# switch.net
KiCad netlist of a schematic drawn in Altium Designer
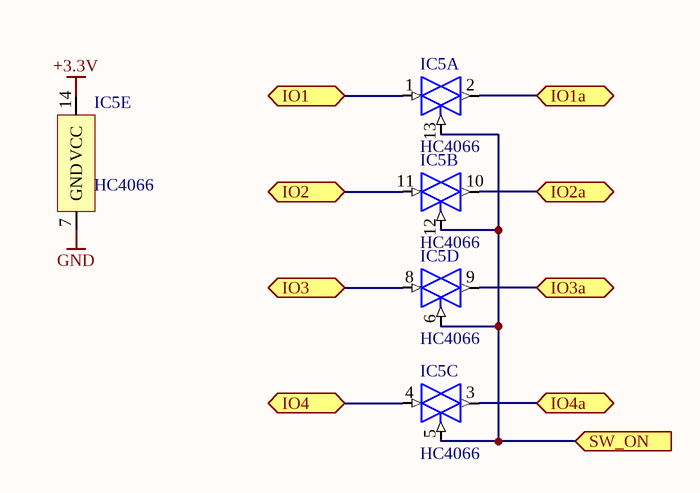
[diagram p0: switch.SchDoc]

(export (version "E")
  (design (tool "Eeschema 10.0.6"))
  (components
    (comp (ref "IC5")
      (value "HC4066")
      (footprint "SO-14")
      (description "CMOS switches")
      (libsource (lib "LIBRARY_SCH") (part "4066"))
    )
  )
  (nets
    (net (code "1") (name "+3.3V") (class "Default")
      (node (ref "IC5") (pin "14") (pinfunction "VCC_14") (pintype "power_in"))
    )
    (net (code "2") (name "/IO1") (class "Default") (node (ref "IC5") (pin "1") (pintype "input")))
    (net (code "3") (name "/IO1a") (class "Default") (node (ref "IC5") (pin "2") (pintype "output")))
    (net (code "4") (name "/IO2") (class "Default") (node (ref "IC5") (pin "11") (pintype "input")))
    (net (code "5") (name "/IO2a") (class "Default") (node (ref "IC5") (pin "10") (pintype "output")))
    (net (code "6") (name "/IO3") (class "Default") (node (ref "IC5") (pin "8") (pintype "input")))
    (net (code "7") (name "/IO3a") (class "Default") (node (ref "IC5") (pin "9") (pintype "output")))
    (net (code "8") (name "/IO4") (class "Default") (node (ref "IC5") (pin "4") (pintype "input")))
    (net (code "9") (name "/IO4a") (class "Default") (node (ref "IC5") (pin "3") (pintype "output")))
    (net (code "10") (name "/SW_ON") (class "Default")
      (node (ref "IC5") (pin "12") (pintype "input"))
      (node (ref "IC5") (pin "13") (pintype "input"))
      (node (ref "IC5") (pin "5") (pintype "input"))
      (node (ref "IC5") (pin "6") (pintype "input"))
    )
    (net (code "11") (name "GND") (class "Default")
      (node (ref "IC5") (pin "7") (pinfunction "GND_7") (pintype "power_in"))
    )
  )
)
